# placa_sch.net
KiCad netlist of a schematic drawn in EasyEDA Pro
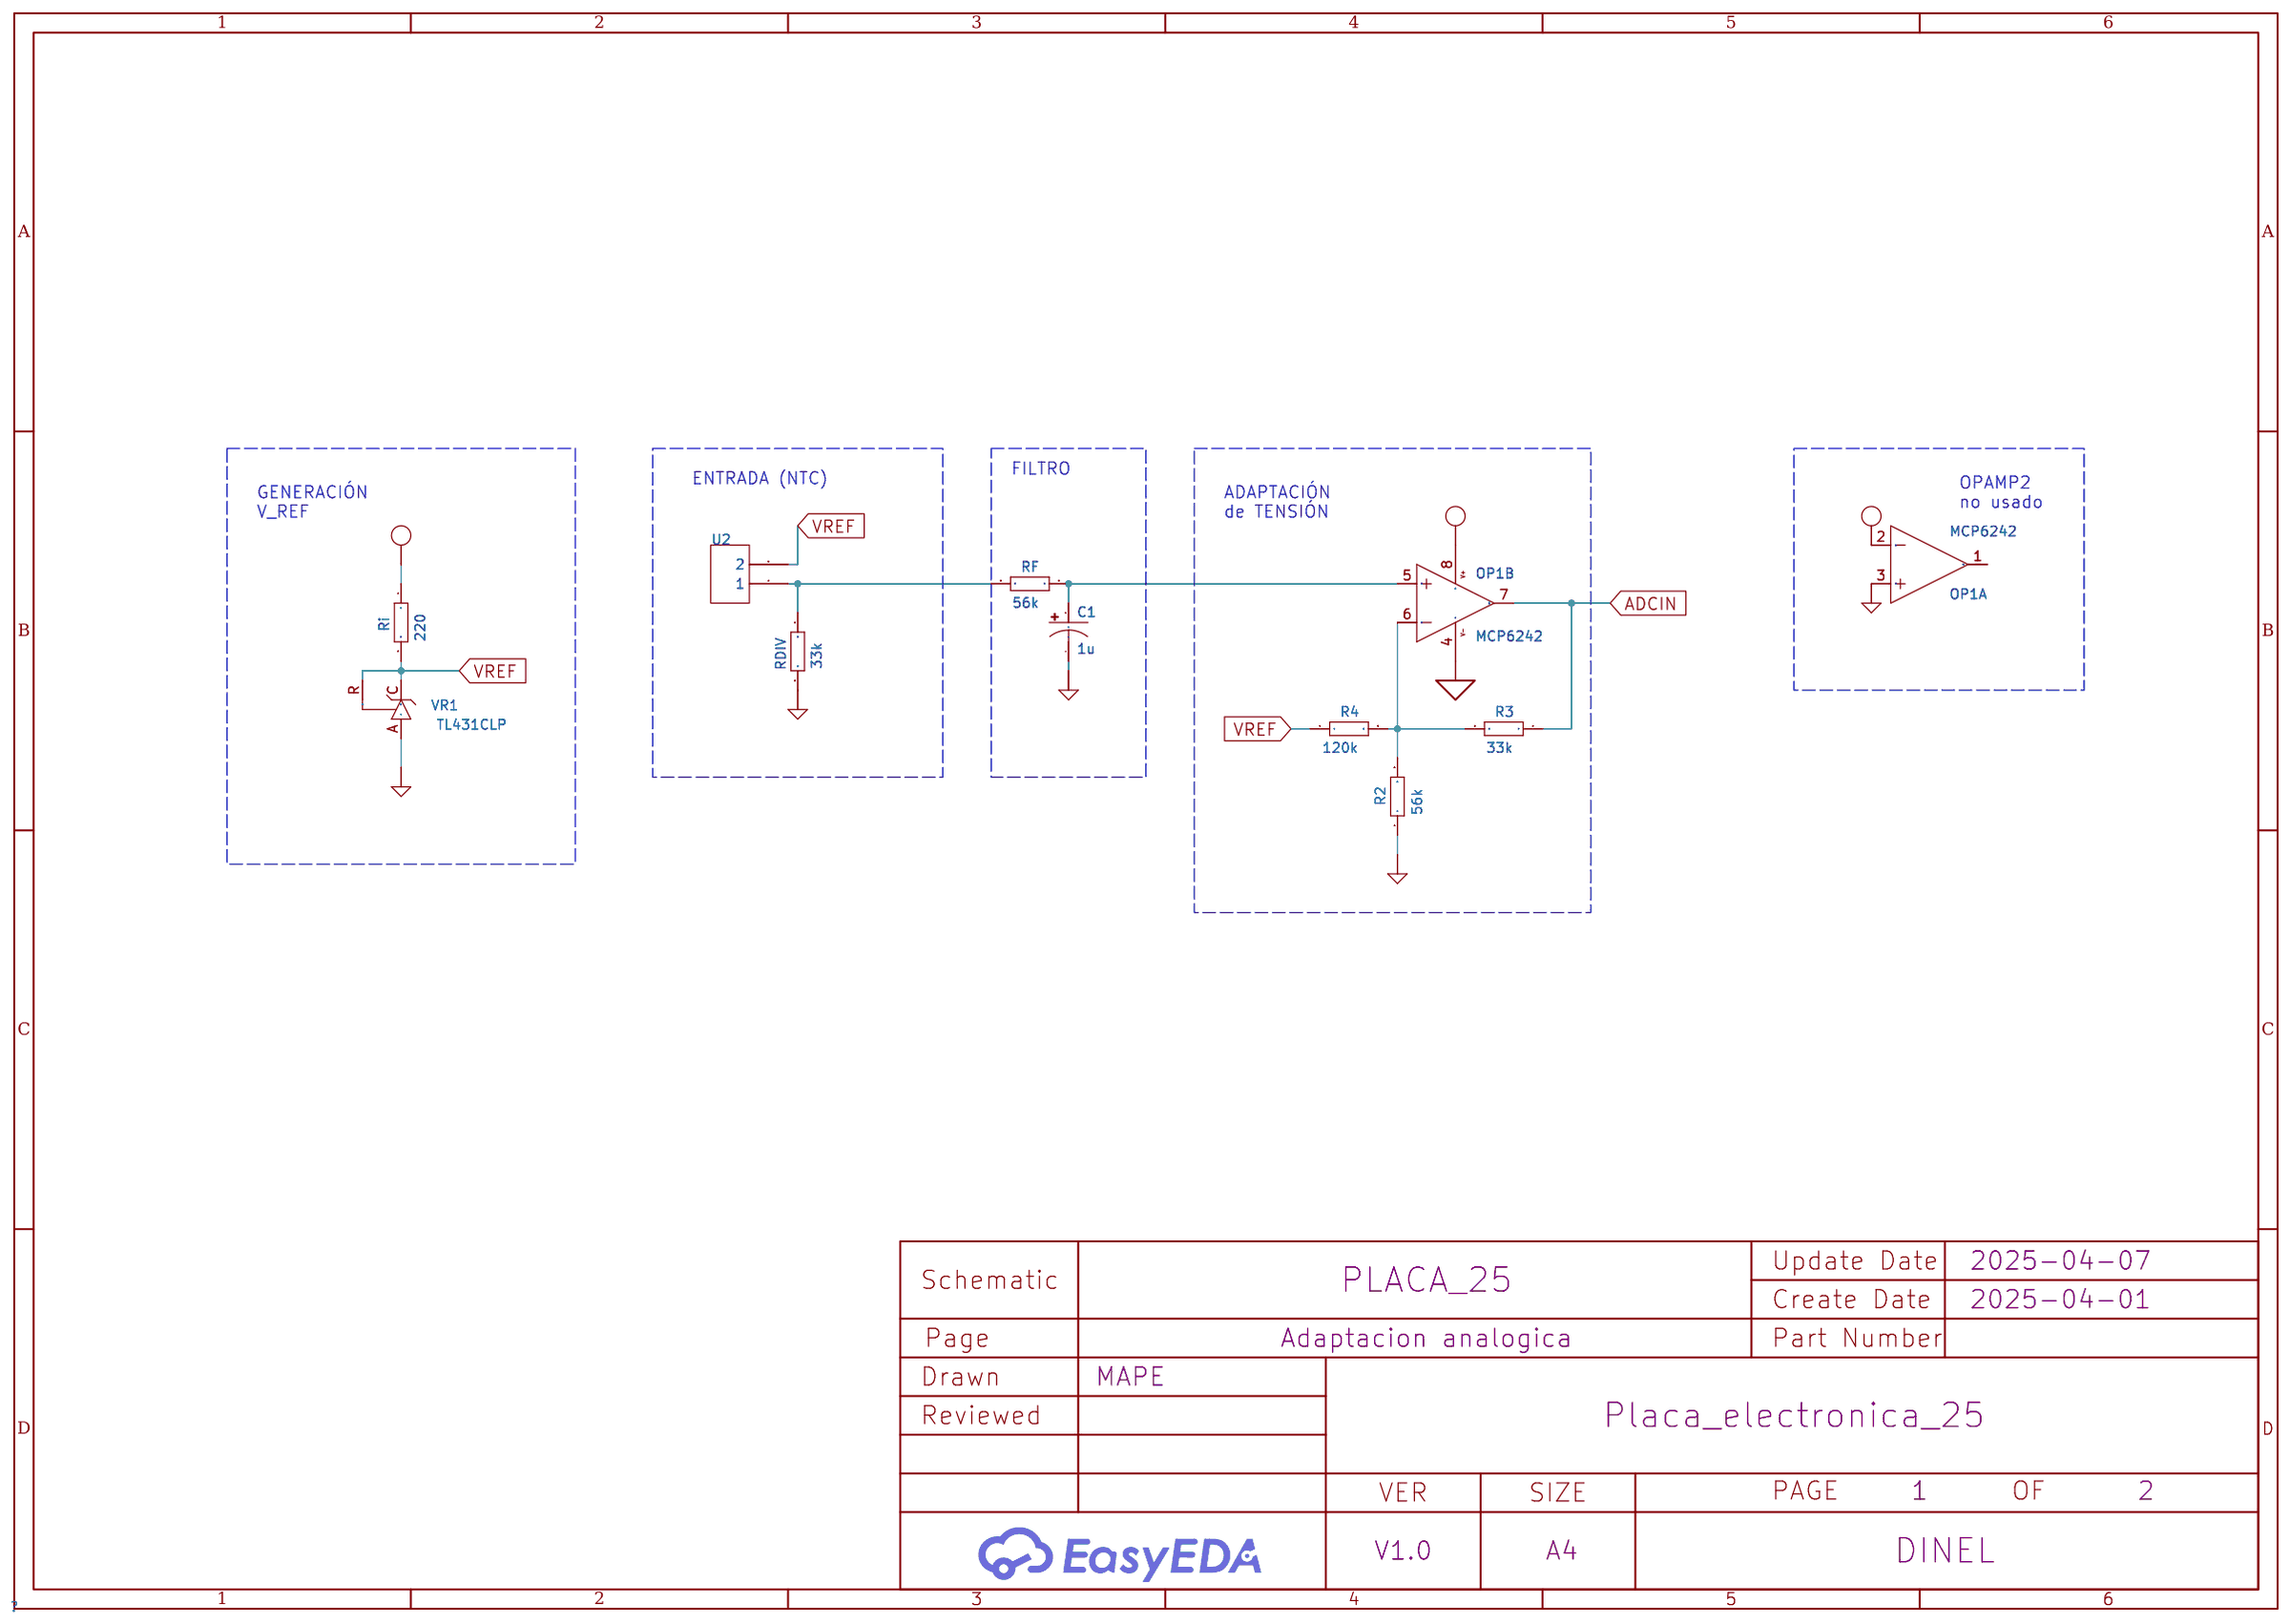
[diagram p0: Adaptacion analogica]
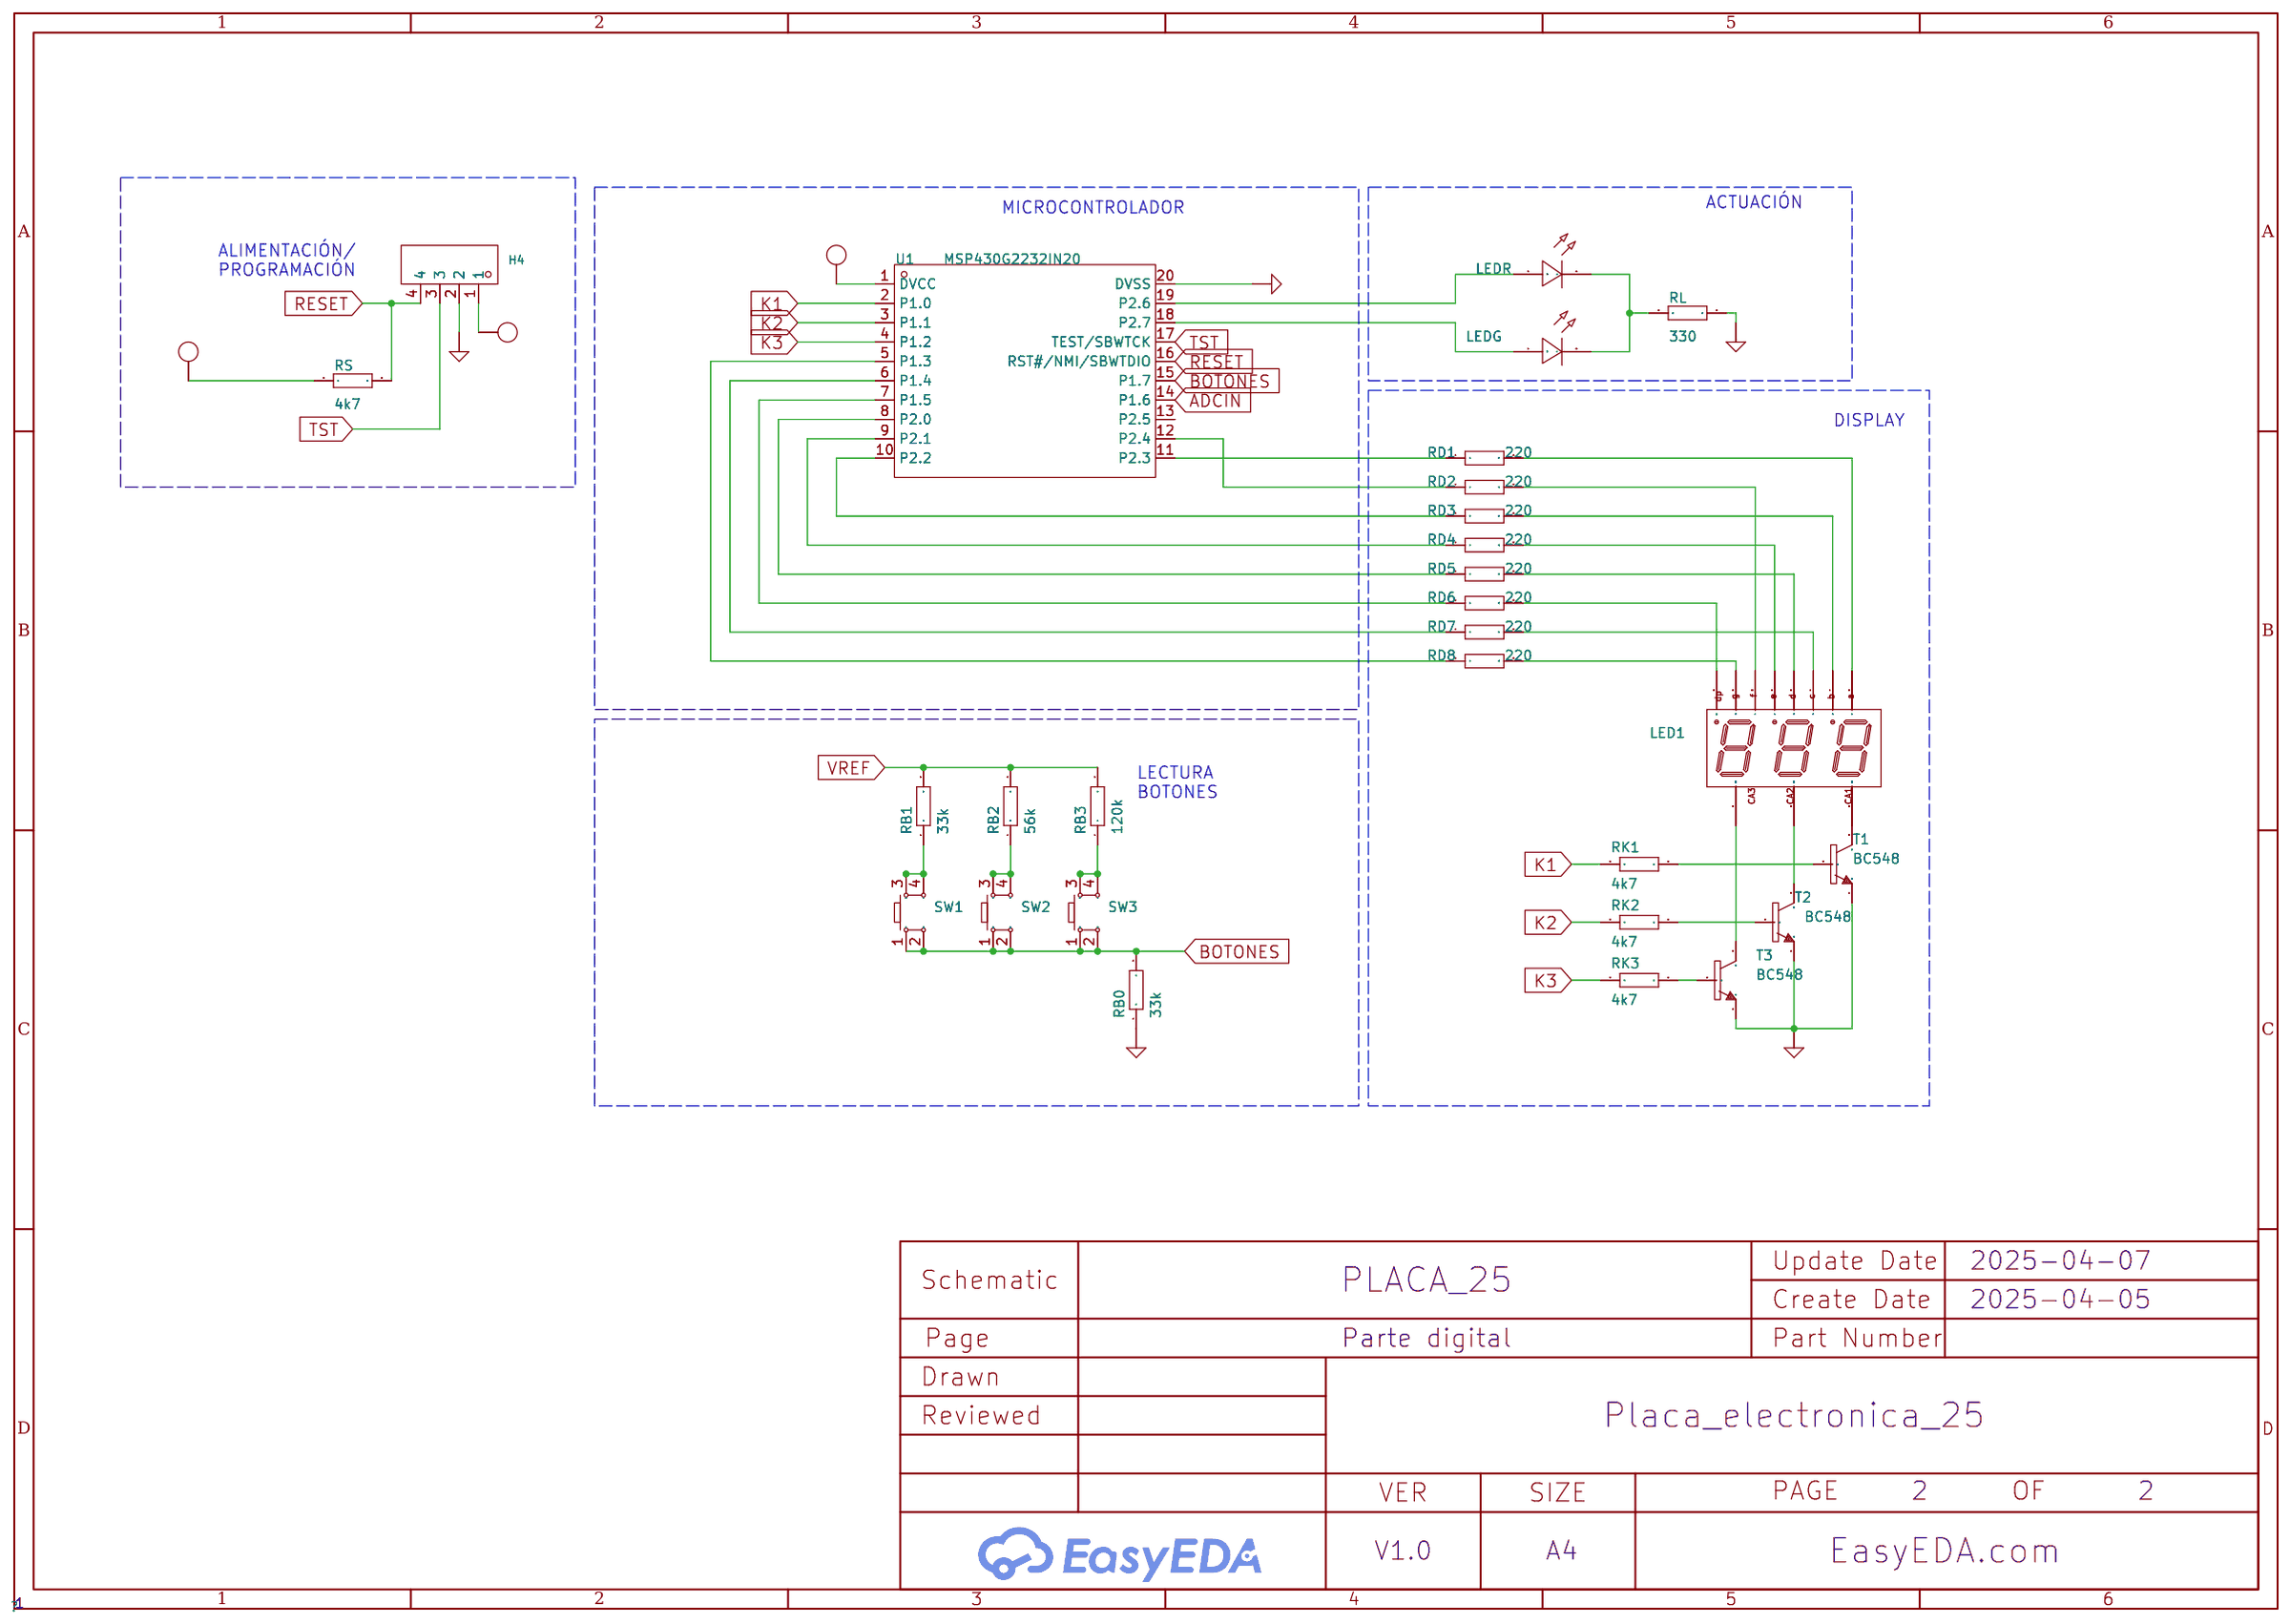
[diagram p1: Parte digital]

(export (version "E")
  (design (tool "Eeschema 10.0.6"))
  (components
    (comp (ref "C1") (value "1u") (libsource (lib "easyedapro") (part "rcl_CPOL-US_E2,5-6E")))
    (comp (ref "OP1") (value "MCP6242") (libsource (lib "easyedapro") (part "linear_MCP6242_CONPADGORDO")))
    (comp (ref "R2") (value "56k") (libsource (lib "easyedapro") (part "resistor_mod2_R-EU__0207/10")))
    (comp (ref "R3") (value "33k") (libsource (lib "easyedapro") (part "resistor_mod2_R-EU__0207/10")))
    (comp (ref "R4") (value "120k") (libsource (lib "easyedapro") (part "resistor_mod2_R-EU__0207/10")))
    (comp (ref "RDIV") (value "33k") (libsource (lib "easyedapro") (part "resistor_mod2_R-EU__0207/10")))
    (comp (ref "RF") (value "56k") (libsource (lib "easyedapro") (part "resistor_mod2_R-EU__0207/10")))
    (comp (ref "Ri") (value "220") (libsource (lib "easyedapro") (part "resistor_mod2_R-EU__0207/10")))
    (comp (ref "U2")
      (value "~")
      (footprint "easyedapro:5.08mm pitch connector")
      (description "RS: 361-7544")
      (libsource (lib "easyedapro") (part "5.08mm pitch connector"))
    )
    (comp (ref "VR1") (value "TL431CLP") (libsource (lib "easyedapro") (part "placa2caras_CTO4_TL431CLP_")))
    (comp (ref "H4")
      (value "~")
      (footprint "easyedapro:HDR-TH_4P-P2.54-V-F")
      (libsource (lib "easyedapro") (part "2.54-1*4P母"))
    )
    (comp (ref "LED1")
      (value "B?56-12EWAA")
      (libsource (lib "easyedapro") (part "display-kingbright_B?56-12*WA_A"))
    )
    (comp (ref "LEDG")
      (value "~")
      (footprint "easyedapro:LED-TH_BD5.8-P2.54-FD")
      (libsource (lib "easyedapro") (part "LED_TH-R"))
    )
    (comp (ref "LEDR")
      (value "~")
      (footprint "easyedapro:LED-TH_BD5.8-P2.54-FD")
      (libsource (lib "easyedapro") (part "LED_TH-R"))
    )
    (comp (ref "RB0") (value "33k") (libsource (lib "easyedapro") (part "resistor_mod2_R-EU__0207/10")))
    (comp (ref "RB1") (value "33k") (libsource (lib "easyedapro") (part "resistor_mod2_R-EU__0207/10")))
    (comp (ref "RB2") (value "56k") (libsource (lib "easyedapro") (part "resistor_mod2_R-EU__0207/10")))
    (comp (ref "RB3") (value "120k") (libsource (lib "easyedapro") (part "resistor_mod2_R-EU__0207/10")))
    (comp (ref "RD1") (value "220") (libsource (lib "easyedapro") (part "resistor_mod2_R-EU__0207/10")))
    (comp (ref "RD2") (value "220") (libsource (lib "easyedapro") (part "resistor_mod2_R-EU__0207/10")))
    (comp (ref "RD3") (value "220") (libsource (lib "easyedapro") (part "resistor_mod2_R-EU__0207/10")))
    (comp (ref "RD4") (value "220") (libsource (lib "easyedapro") (part "resistor_mod2_R-EU__0207/10")))
    (comp (ref "RD5") (value "220") (libsource (lib "easyedapro") (part "resistor_mod2_R-EU__0207/10")))
    (comp (ref "RD6") (value "220") (libsource (lib "easyedapro") (part "resistor_mod2_R-EU__0207/10")))
    (comp (ref "RD7") (value "220") (libsource (lib "easyedapro") (part "resistor_mod2_R-EU__0207/10")))
    (comp (ref "RD8") (value "220") (libsource (lib "easyedapro") (part "resistor_mod2_R-EU__0207/10")))
    (comp (ref "RK1") (value "4k7") (libsource (lib "easyedapro") (part "resistor_mod2_R-EU__0207/10")))
    (comp (ref "RK2") (value "4k7") (libsource (lib "easyedapro") (part "resistor_mod2_R-EU__0207/10")))
    (comp (ref "RK3") (value "4k7") (libsource (lib "easyedapro") (part "resistor_mod2_R-EU__0207/10")))
    (comp (ref "RL") (value "330") (libsource (lib "easyedapro") (part "resistor_mod2_R-EU__0207/10")))
    (comp (ref "RS") (value "4k7") (libsource (lib "easyedapro") (part "resistor_mod2_R-EU__0207/10")))
    (comp (ref "SW1")
      (value "~")
      (footprint "easyedapro:KEY-TH_4P-L6.0-W6.0-P3.90-LS6.5")
      (libsource (lib "easyedapro") (part "轻触按键"))
    )
    (comp (ref "SW2")
      (value "~")
      (footprint "easyedapro:KEY-TH_4P-L6.0-W6.0-P3.90-LS6.5")
      (libsource (lib "easyedapro") (part "轻触按键"))
    )
    (comp (ref "SW3")
      (value "~")
      (footprint "easyedapro:KEY-TH_4P-L6.0-W6.0-P3.90-LS6.5")
      (libsource (lib "easyedapro") (part "轻触按键"))
    )
    (comp (ref "T1") (value "BC548") (libsource (lib "easyedapro") (part "transistor-npn_BC548*_")))
    (comp (ref "T2") (value "BC548") (libsource (lib "easyedapro") (part "transistor-npn_BC548*_")))
    (comp (ref "T3") (value "BC548") (libsource (lib "easyedapro") (part "transistor-npn_BC548*_")))
    (comp (ref "U1")
      (value "MSP430G2232IN20")
      (footprint "easyedapro:PDIP-20_L25.4-W6.4-P2.54-LS7.6-BL")
      (fields (field (name "Manufacturer") "TI(德州仪器)"))
      (libsource (lib "easyedapro") (part "MSP430G2232IN20"))
    )
  )
  (nets
    (net (code "1") (name "ADCIN") (class "Default")
      (node (ref "OP1") (pin "7") (pinfunction "OUT_7") (pintype "output"))
      (node (ref "R3") (pin "1") (pinfunction "1_1") (pintype "unspecified"))
      (node (ref "U1") (pin "14") (pinfunction "P1.6_14") (pintype "unspecified"))
    )
    (net (code "2") (name "BOTONES") (class "Default")
      (node (ref "RB0") (pin "2") (pinfunction "2_2") (pintype "unspecified"))
      (node (ref "SW1") (pin "1") (pinfunction "1_1") (pintype "input"))
      (node (ref "SW1") (pin "2") (pinfunction "2_2") (pintype "input"))
      (node (ref "SW2") (pin "1") (pinfunction "1_1") (pintype "input"))
      (node (ref "SW2") (pin "2") (pinfunction "2_2") (pintype "input"))
      (node (ref "SW3") (pin "1") (pinfunction "1_1") (pintype "input"))
      (node (ref "SW3") (pin "2") (pinfunction "2_2") (pintype "input"))
      (node (ref "U1") (pin "15") (pinfunction "P1.7_15") (pintype "unspecified"))
    )
    (net (code "3") (name "GND") (class "Default")
      (node (ref "C1") (pin "-") (pinfunction "-_-") (pintype "unspecified"))
      (node (ref "H4") (pin "2") (pinfunction "2_2") (pintype "input"))
      (node (ref "OP1") (pin "3") (pinfunction "+IN_3") (pintype "input"))
      (node (ref "OP1") (pin "4") (pinfunction "V-_4") (pintype "unspecified"))
      (node (ref "R2") (pin "1") (pinfunction "1_1") (pintype "unspecified"))
      (node (ref "RB0") (pin "1") (pinfunction "1_1") (pintype "unspecified"))
      (node (ref "RDIV") (pin "2") (pinfunction "2_2") (pintype "unspecified"))
      (node (ref "RL") (pin "1") (pinfunction "1_1") (pintype "unspecified"))
      (node (ref "T1") (pin "E") (pinfunction "E_E") (pintype "unspecified"))
      (node (ref "T2") (pin "E") (pinfunction "E_E") (pintype "unspecified"))
      (node (ref "T3") (pin "E") (pinfunction "E_E") (pintype "unspecified"))
      (node (ref "U1") (pin "20") (pinfunction "DVSS_20") (pintype "unspecified"))
      (node (ref "VR1") (pin "A") (pinfunction "A_A") (pintype "unspecified"))
    )
    (net (code "4") (name "K1") (class "Default")
      (node (ref "RK1") (pin "1") (pinfunction "1_1") (pintype "unspecified"))
      (node (ref "U1") (pin "2") (pinfunction "P1.0_2") (pintype "unspecified"))
    )
    (net (code "5") (name "K2") (class "Default")
      (node (ref "RK2") (pin "1") (pinfunction "1_1") (pintype "unspecified"))
      (node (ref "U1") (pin "3") (pinfunction "P1.1_3") (pintype "unspecified"))
    )
    (net (code "6") (name "K3") (class "Default")
      (node (ref "RK3") (pin "1") (pinfunction "1_1") (pintype "unspecified"))
      (node (ref "U1") (pin "4") (pinfunction "P1.2_4") (pintype "unspecified"))
    )
    (net (code "7") (name "Net-(LED1-A)") (class "Default")
      (node (ref "LED1") (pin "11") (pinfunction "A_11") (pintype "unspecified"))
      (node (ref "RD1") (pin "2") (pinfunction "2_2") (pintype "unspecified"))
    )
    (net (code "8") (name "Net-(LED1-B)") (class "Default")
      (node (ref "LED1") (pin "7") (pinfunction "B_7") (pintype "unspecified"))
      (node (ref "RD3") (pin "2") (pinfunction "2_2") (pintype "unspecified"))
    )
    (net (code "9") (name "Net-(LED1-C)") (class "Default")
      (node (ref "LED1") (pin "4") (pinfunction "C_4") (pintype "unspecified"))
      (node (ref "RD7") (pin "2") (pinfunction "2_2") (pintype "unspecified"))
    )
    (net (code "10") (name "Net-(LED1-CA@1)") (class "Default")
      (node (ref "LED1") (pin "12") (pinfunction "CA@1_12") (pintype "unspecified"))
      (node (ref "T1") (pin "C") (pinfunction "C_C") (pintype "unspecified"))
    )
    (net (code "11") (name "Net-(LED1-CA@2)") (class "Default")
      (node (ref "LED1") (pin "9") (pinfunction "CA@2_9") (pintype "unspecified"))
      (node (ref "T2") (pin "C") (pinfunction "C_C") (pintype "unspecified"))
    )
    (net (code "12") (name "Net-(LED1-CA@3)") (class "Default")
      (node (ref "LED1") (pin "8") (pinfunction "CA@3_8") (pintype "unspecified"))
      (node (ref "T3") (pin "C") (pinfunction "C_C") (pintype "unspecified"))
    )
    (net (code "13") (name "Net-(LED1-D)") (class "Default")
      (node (ref "LED1") (pin "2") (pinfunction "D_2") (pintype "unspecified"))
      (node (ref "RD5") (pin "2") (pinfunction "2_2") (pintype "unspecified"))
    )
    (net (code "14") (name "Net-(LED1-DP)") (class "Default")
      (node (ref "LED1") (pin "3") (pinfunction "DP_3") (pintype "unspecified"))
      (node (ref "RD6") (pin "2") (pinfunction "2_2") (pintype "unspecified"))
    )
    (net (code "15") (name "Net-(LED1-E)") (class "Default")
      (node (ref "LED1") (pin "1") (pinfunction "E_1") (pintype "unspecified"))
      (node (ref "RD4") (pin "2") (pinfunction "2_2") (pintype "unspecified"))
    )
    (net (code "16") (name "Net-(LED1-F)") (class "Default")
      (node (ref "LED1") (pin "10") (pinfunction "F_10") (pintype "unspecified"))
      (node (ref "RD2") (pin "2") (pinfunction "2_2") (pintype "unspecified"))
    )
    (net (code "17") (name "Net-(LED1-G)") (class "Default")
      (node (ref "LED1") (pin "5") (pinfunction "G_5") (pintype "unspecified"))
      (node (ref "RD8") (pin "2") (pinfunction "2_2") (pintype "unspecified"))
    )
    (net (code "18") (name "Net-(LEDG-A)") (class "Default")
      (node (ref "LEDG") (pin "2") (pinfunction "A_2") (pintype "input"))
      (node (ref "LEDR") (pin "2") (pinfunction "A_2") (pintype "input"))
      (node (ref "RL") (pin "2") (pinfunction "2_2") (pintype "unspecified"))
    )
    (net (code "19") (name "Net-(LEDG-C)") (class "Default")
      (node (ref "LEDG") (pin "1") (pinfunction "C_1") (pintype "input"))
      (node (ref "U1") (pin "18") (pinfunction "P2.7_18") (pintype "unspecified"))
    )
    (net (code "20") (name "Net-(LEDR-C)") (class "Default")
      (node (ref "LEDR") (pin "1") (pinfunction "C_1") (pintype "input"))
      (node (ref "U1") (pin "19") (pinfunction "P2.6_19") (pintype "unspecified"))
    )
    (net (code "21") (name "Net-(OP1B-+IN)") (class "Default")
      (node (ref "C1") (pin "+") (pinfunction "+_+") (pintype "unspecified"))
      (node (ref "OP1") (pin "5") (pinfunction "+IN_5") (pintype "input"))
      (node (ref "RF") (pin "1") (pinfunction "1_1") (pintype "unspecified"))
    )
    (net (code "22") (name "Net-(OP1B--IN)") (class "Default")
      (node (ref "OP1") (pin "6") (pinfunction "-IN_6") (pintype "input"))
      (node (ref "R2") (pin "2") (pinfunction "2_2") (pintype "unspecified"))
      (node (ref "R3") (pin "2") (pinfunction "2_2") (pintype "unspecified"))
      (node (ref "R4") (pin "2") (pinfunction "2_2") (pintype "unspecified"))
    )
    (net (code "23") (name "Net-(RB1-Pad1)") (class "Default")
      (node (ref "RB1") (pin "1") (pinfunction "1_1") (pintype "unspecified"))
      (node (ref "SW1") (pin "3") (pinfunction "3_3") (pintype "input"))
      (node (ref "SW1") (pin "4") (pinfunction "4_4") (pintype "input"))
    )
    (net (code "24") (name "Net-(RB2-Pad1)") (class "Default")
      (node (ref "RB2") (pin "1") (pinfunction "1_1") (pintype "unspecified"))
      (node (ref "SW2") (pin "3") (pinfunction "3_3") (pintype "input"))
      (node (ref "SW2") (pin "4") (pinfunction "4_4") (pintype "input"))
    )
    (net (code "25") (name "Net-(RB3-Pad1)") (class "Default")
      (node (ref "RB3") (pin "1") (pinfunction "1_1") (pintype "unspecified"))
      (node (ref "SW3") (pin "3") (pinfunction "3_3") (pintype "input"))
      (node (ref "SW3") (pin "4") (pinfunction "4_4") (pintype "input"))
    )
    (net (code "26") (name "Net-(RDIV-Pad1)") (class "Default")
      (node (ref "RDIV") (pin "1") (pinfunction "1_1") (pintype "unspecified"))
      (node (ref "RF") (pin "2") (pinfunction "2_2") (pintype "unspecified"))
      (node (ref "U2") (pin "1") (pinfunction "1_1") (pintype "input"))
    )
    (net (code "27") (name "Net-(RK1-Pad2)") (class "Default")
      (node (ref "RK1") (pin "2") (pinfunction "2_2") (pintype "unspecified"))
      (node (ref "T1") (pin "B") (pinfunction "B_B") (pintype "unspecified"))
    )
    (net (code "28") (name "Net-(RK2-Pad2)") (class "Default")
      (node (ref "RK2") (pin "2") (pinfunction "2_2") (pintype "unspecified"))
      (node (ref "T2") (pin "B") (pinfunction "B_B") (pintype "unspecified"))
    )
    (net (code "29") (name "Net-(RK3-Pad2)") (class "Default")
      (node (ref "RK3") (pin "2") (pinfunction "2_2") (pintype "unspecified"))
      (node (ref "T3") (pin "B") (pinfunction "B_B") (pintype "unspecified"))
    )
    (net (code "30") (name "Net-(U1-P1.3)") (class "Default")
      (node (ref "RD8") (pin "1") (pinfunction "1_1") (pintype "unspecified"))
      (node (ref "U1") (pin "5") (pinfunction "P1.3_5") (pintype "unspecified"))
    )
    (net (code "31") (name "Net-(U1-P1.4)") (class "Default")
      (node (ref "RD7") (pin "1") (pinfunction "1_1") (pintype "unspecified"))
      (node (ref "U1") (pin "6") (pinfunction "P1.4_6") (pintype "unspecified"))
    )
    (net (code "32") (name "Net-(U1-P1.5)") (class "Default")
      (node (ref "RD6") (pin "1") (pinfunction "1_1") (pintype "unspecified"))
      (node (ref "U1") (pin "7") (pinfunction "P1.5_7") (pintype "unspecified"))
    )
    (net (code "33") (name "Net-(U1-P2.0)") (class "Default")
      (node (ref "RD5") (pin "1") (pinfunction "1_1") (pintype "unspecified"))
      (node (ref "U1") (pin "8") (pinfunction "P2.0_8") (pintype "unspecified"))
    )
    (net (code "34") (name "Net-(U1-P2.1)") (class "Default")
      (node (ref "RD4") (pin "1") (pinfunction "1_1") (pintype "unspecified"))
      (node (ref "U1") (pin "9") (pinfunction "P2.1_9") (pintype "unspecified"))
    )
    (net (code "35") (name "Net-(U1-P2.2)") (class "Default")
      (node (ref "RD3") (pin "1") (pinfunction "1_1") (pintype "unspecified"))
      (node (ref "U1") (pin "10") (pinfunction "P2.2_10") (pintype "unspecified"))
    )
    (net (code "36") (name "Net-(U1-P2.3)") (class "Default")
      (node (ref "RD1") (pin "1") (pinfunction "1_1") (pintype "unspecified"))
      (node (ref "U1") (pin "11") (pinfunction "P2.3_11") (pintype "unspecified"))
    )
    (net (code "37") (name "Net-(U1-P2.4)") (class "Default")
      (node (ref "RD2") (pin "1") (pinfunction "1_1") (pintype "unspecified"))
      (node (ref "U1") (pin "12") (pinfunction "P2.4_12") (pintype "unspecified"))
    )
    (net (code "38") (name "RESET") (class "Default")
      (node (ref "H4") (pin "4") (pinfunction "4_4") (pintype "input"))
      (node (ref "RS") (pin "2") (pinfunction "2_2") (pintype "unspecified"))
      (node (ref "U1") (pin "16") (pinfunction "RST#/NMI/SBWTDIO_16") (pintype "unspecified"))
    )
    (net (code "39") (name "TST") (class "Default")
      (node (ref "H4") (pin "3") (pinfunction "3_3") (pintype "input"))
      (node (ref "U1") (pin "17") (pinfunction "TEST/SBWTCK_17") (pintype "unspecified"))
    )
    (net (code "40") (name "VCC") (class "Default")
      (node (ref "H4") (pin "1") (pinfunction "1_1") (pintype "input"))
      (node (ref "OP1") (pin "2") (pinfunction "-IN_2") (pintype "input"))
      (node (ref "OP1") (pin "8") (pinfunction "V+_8") (pintype "unspecified"))
      (node (ref "RS") (pin "1") (pinfunction "1_1") (pintype "unspecified"))
      (node (ref "Ri") (pin "1") (pinfunction "1_1") (pintype "unspecified"))
      (node (ref "U1") (pin "1") (pinfunction "DVCC_1") (pintype "unspecified"))
    )
    (net (code "41") (name "VREF") (class "Default")
      (node (ref "R4") (pin "1") (pinfunction "1_1") (pintype "unspecified"))
      (node (ref "RB1") (pin "2") (pinfunction "2_2") (pintype "unspecified"))
      (node (ref "RB2") (pin "2") (pinfunction "2_2") (pintype "unspecified"))
      (node (ref "RB3") (pin "2") (pinfunction "2_2") (pintype "unspecified"))
      (node (ref "Ri") (pin "2") (pinfunction "2_2") (pintype "unspecified"))
      (node (ref "U2") (pin "2") (pinfunction "2_2") (pintype "input"))
      (node (ref "VR1") (pin "C") (pinfunction "C_C") (pintype "unspecified"))
      (node (ref "VR1") (pin "R") (pinfunction "R_R") (pintype "unspecified"))
    )
    (net (code "42") (name "unconnected-(OP1A-OUT-Pad1)") (class "Default")
      (node (ref "OP1") (pin "1") (pinfunction "OUT_1") (pintype "output"))
    )
    (net (code "43") (name "unconnected-(U1-P2.5-Pad13)") (class "Default")
      (node (ref "U1") (pin "13") (pinfunction "P2.5_13") (pintype "unspecified"))
    )
  )
)
